# 14_-_ETHERNET_10_100_1000.net
KiCad netlist of a schematic drawn in Altium Designer
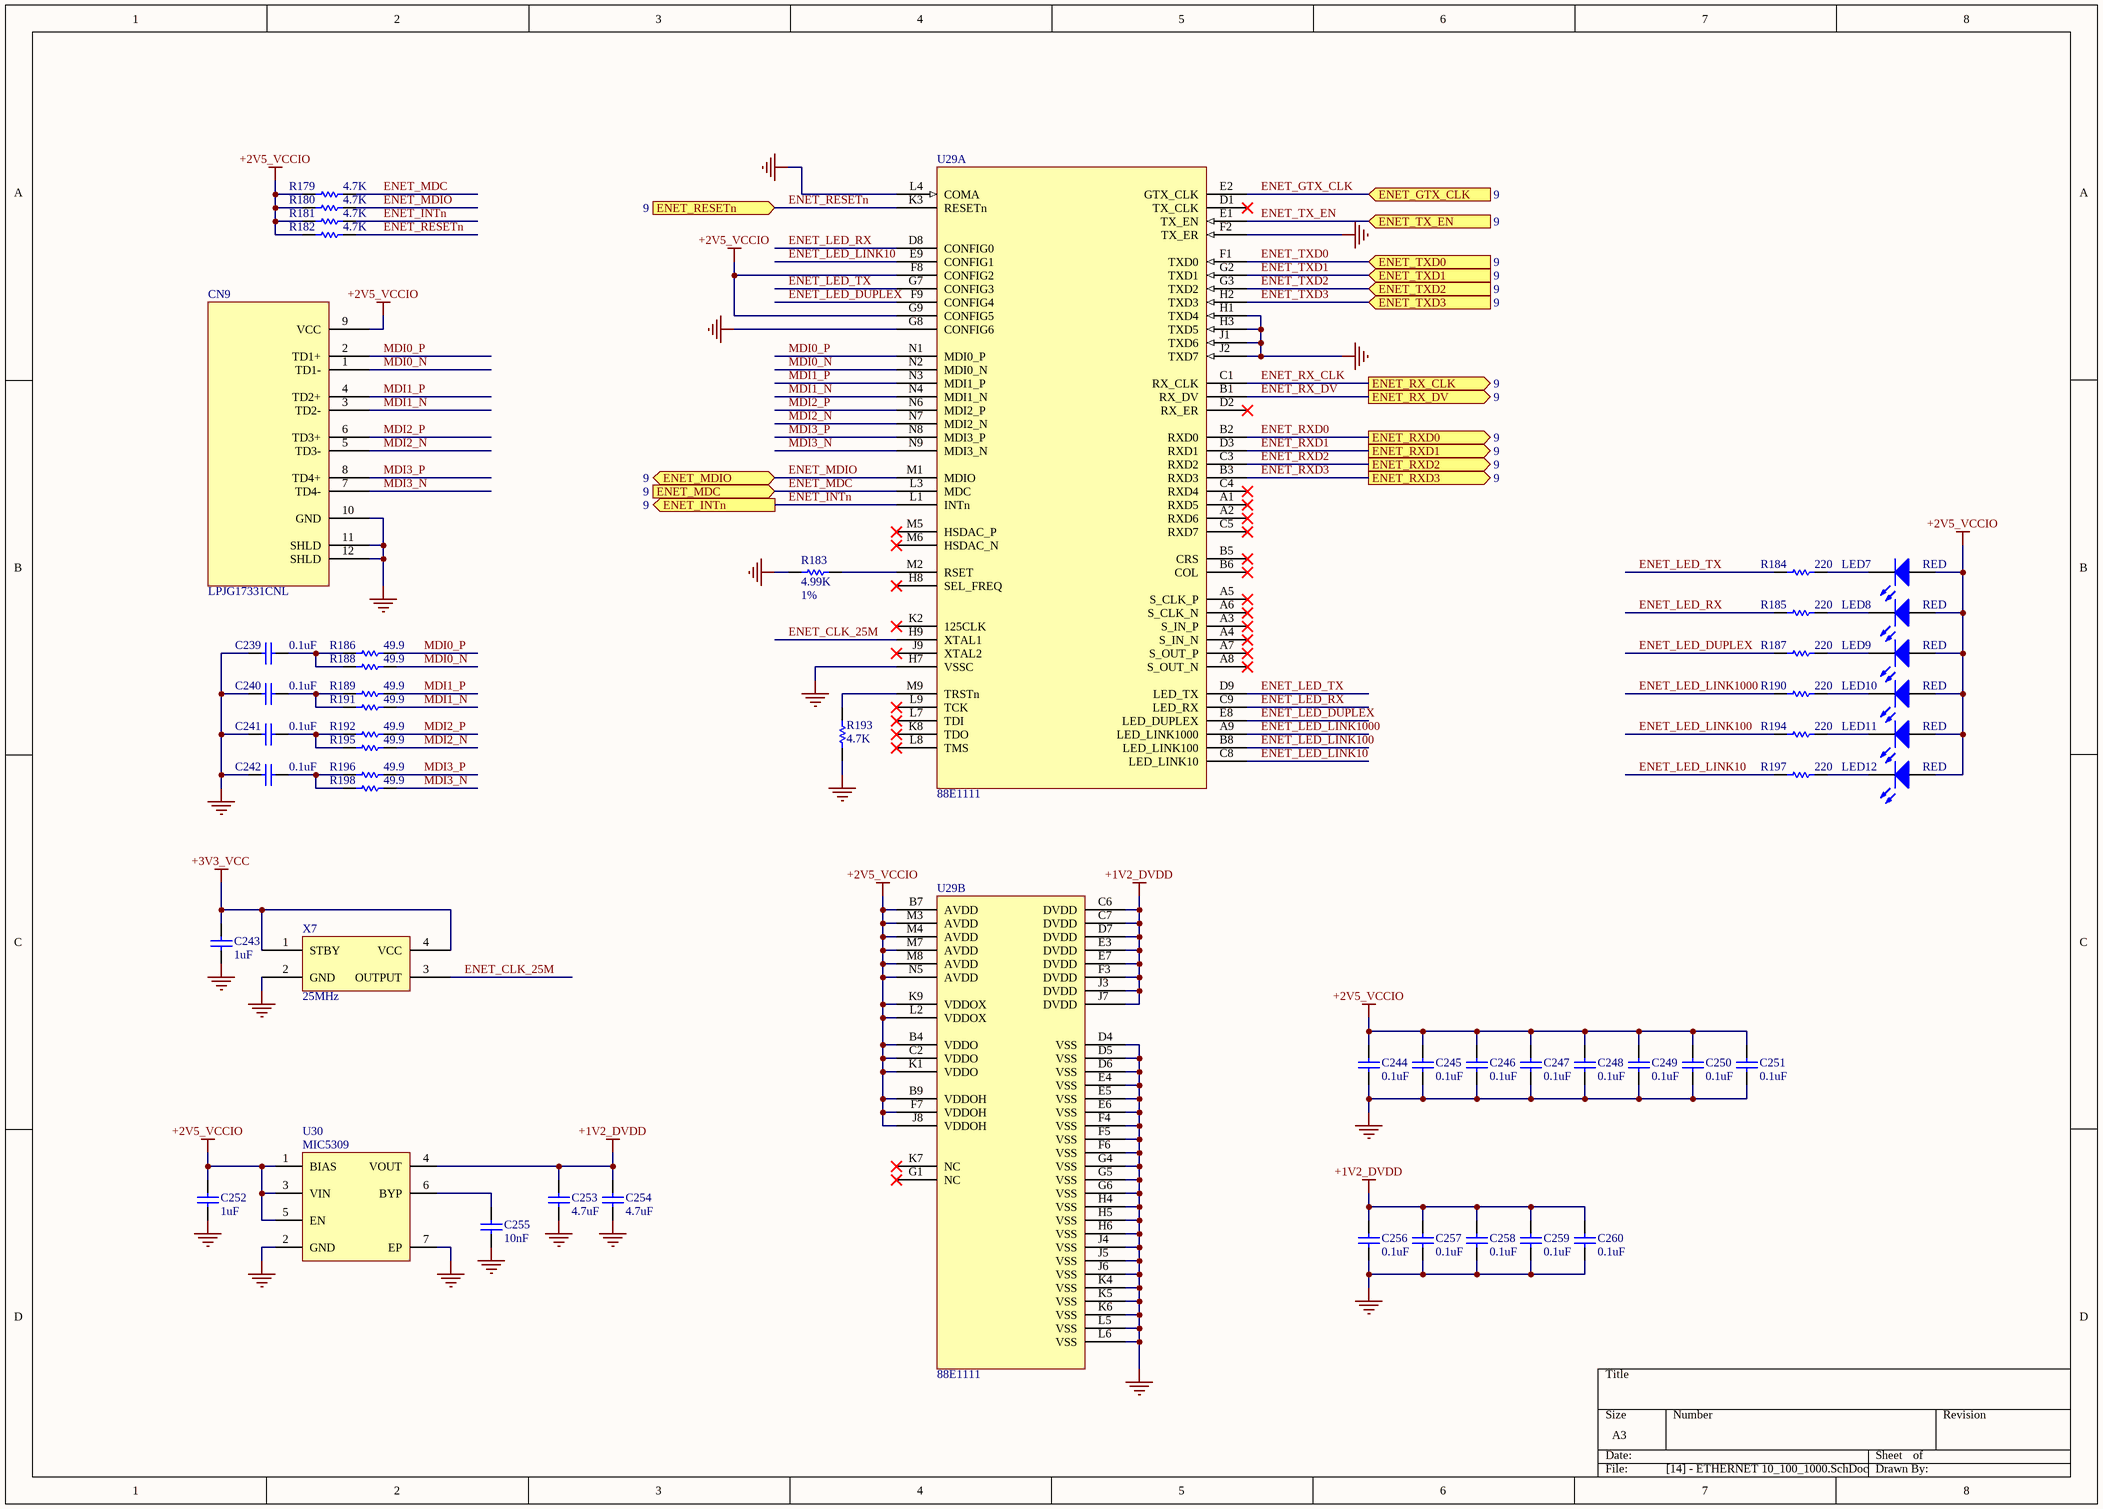
[diagram p0: [14] - ETHERNET 10_100_1000.SchDoc]

(export (version "E")
  (design (tool "Eeschema 10.0.6"))
  (components
    (comp (ref "C239")
      (value "0.1uF")
      (footprint "0402_C")
      (description "Non-Pol SMD Capacitor")
      (libsource (lib "Passive Components") (part "Cap SMD"))
    )
    (comp (ref "C240")
      (value "0.1uF")
      (footprint "0402_C")
      (description "Non-Pol SMD Capacitor")
      (libsource (lib "Passive Components") (part "Cap SMD"))
    )
    (comp (ref "C241")
      (value "0.1uF")
      (footprint "0402_C")
      (description "Non-Pol SMD Capacitor")
      (libsource (lib "Passive Components") (part "Cap SMD"))
    )
    (comp (ref "C242")
      (value "0.1uF")
      (footprint "0402_C")
      (description "Non-Pol SMD Capacitor")
      (libsource (lib "Passive Components") (part "Cap SMD"))
    )
    (comp (ref "C243")
      (value "1uF")
      (footprint "0402_C")
      (description "Non-Pol SMD Capacitor")
      (libsource (lib "Passive Components") (part "Cap SMD"))
    )
    (comp (ref "C244")
      (value "0.1uF")
      (footprint "0402_C")
      (description "Non-Pol SMD Capacitor")
      (libsource (lib "Passive Components") (part "Cap SMD"))
    )
    (comp (ref "C245")
      (value "0.1uF")
      (footprint "0402_C")
      (description "Non-Pol SMD Capacitor")
      (libsource (lib "Passive Components") (part "Cap SMD"))
    )
    (comp (ref "C246")
      (value "0.1uF")
      (footprint "0402_C")
      (description "Non-Pol SMD Capacitor")
      (libsource (lib "Passive Components") (part "Cap SMD"))
    )
    (comp (ref "C247")
      (value "0.1uF")
      (footprint "0402_C")
      (description "Non-Pol SMD Capacitor")
      (libsource (lib "Passive Components") (part "Cap SMD"))
    )
    (comp (ref "C248")
      (value "0.1uF")
      (footprint "0402_C")
      (description "Non-Pol SMD Capacitor")
      (libsource (lib "Passive Components") (part "Cap SMD"))
    )
    (comp (ref "C249")
      (value "0.1uF")
      (footprint "0402_C")
      (description "Non-Pol SMD Capacitor")
      (libsource (lib "Passive Components") (part "Cap SMD"))
    )
    (comp (ref "C250")
      (value "0.1uF")
      (footprint "0402_C")
      (description "Non-Pol SMD Capacitor")
      (libsource (lib "Passive Components") (part "Cap SMD"))
    )
    (comp (ref "C251")
      (value "0.1uF")
      (footprint "0402_C")
      (description "Non-Pol SMD Capacitor")
      (libsource (lib "Passive Components") (part "Cap SMD"))
    )
    (comp (ref "C252")
      (value "1uF")
      (footprint "0805_C")
      (description "Non-Pol SMD Capacitor")
      (libsource (lib "Passive Components") (part "Cap SMD"))
    )
    (comp (ref "C253")
      (value "4.7uF")
      (footprint "0805_C")
      (description "Non-Pol SMD Capacitor")
      (libsource (lib "Passive Components") (part "Cap SMD"))
    )
    (comp (ref "C254")
      (value "4.7uF")
      (footprint "0805_C")
      (description "Non-Pol SMD Capacitor")
      (libsource (lib "Passive Components") (part "Cap SMD"))
    )
    (comp (ref "C255")
      (value "10nF")
      (footprint "0805_C")
      (description "Non-Pol SMD Capacitor")
      (libsource (lib "Passive Components") (part "Cap SMD"))
    )
    (comp (ref "C256")
      (value "0.1uF")
      (footprint "0402_C")
      (description "Non-Pol SMD Capacitor")
      (libsource (lib "Passive Components") (part "Cap SMD"))
    )
    (comp (ref "C257")
      (value "0.1uF")
      (footprint "0402_C")
      (description "Non-Pol SMD Capacitor")
      (libsource (lib "Passive Components") (part "Cap SMD"))
    )
    (comp (ref "C258")
      (value "0.1uF")
      (footprint "0402_C")
      (description "Non-Pol SMD Capacitor")
      (libsource (lib "Passive Components") (part "Cap SMD"))
    )
    (comp (ref "C259")
      (value "0.1uF")
      (footprint "0402_C")
      (description "Non-Pol SMD Capacitor")
      (libsource (lib "Passive Components") (part "Cap SMD"))
    )
    (comp (ref "C260")
      (value "0.1uF")
      (footprint "0402_C")
      (description "Non-Pol SMD Capacitor")
      (libsource (lib "Passive Components") (part "Cap SMD"))
    )
    (comp (ref "CN9")
      (value "LPJG17331CNL")
      (footprint "LPJG17331CNL")
      (description "100/1000 Base-T Modular jack RJ45 With Transformer Tab Up Without Led")
      (libsource (lib "Connectors") (part "LPJG17331CNL"))
    )
    (comp (ref "LED7")
      (value "RED")
      (footprint "LED_0603")
      (description "Typical LED")
      (libsource (lib "Common Components") (part "LED"))
    )
    (comp (ref "LED8")
      (value "RED")
      (footprint "LED_0603")
      (description "Typical LED")
      (libsource (lib "Common Components") (part "LED"))
    )
    (comp (ref "LED9")
      (value "RED")
      (footprint "LED_0603")
      (description "Typical LED")
      (libsource (lib "Common Components") (part "LED"))
    )
    (comp (ref "LED10")
      (value "RED")
      (footprint "LED_0603")
      (description "Typical LED")
      (libsource (lib "Common Components") (part "LED"))
    )
    (comp (ref "LED11")
      (value "RED")
      (footprint "LED_0603")
      (description "Typical LED")
      (libsource (lib "Common Components") (part "LED"))
    )
    (comp (ref "LED12")
      (value "RED")
      (footprint "LED_0603")
      (description "Typical LED")
      (libsource (lib "Common Components") (part "LED"))
    )
    (comp (ref "R179")
      (value "4.7K")
      (footprint "0402_R")
      (description "SMD Resistor")
      (fields (field (name "TOLERANCE") "5%"))
      (libsource (lib "Passive Components") (part "Res SMD"))
    )
    (comp (ref "R180")
      (value "4.7K")
      (footprint "0402_R")
      (description "SMD Resistor")
      (fields (field (name "TOLERANCE") "5%"))
      (libsource (lib "Passive Components") (part "Res SMD"))
    )
    (comp (ref "R181")
      (value "4.7K")
      (footprint "0402_R")
      (description "SMD Resistor")
      (fields (field (name "TOLERANCE") "5%"))
      (libsource (lib "Passive Components") (part "Res SMD"))
    )
    (comp (ref "R182")
      (value "4.7K")
      (footprint "0402_R")
      (description "SMD Resistor")
      (fields (field (name "TOLERANCE") "5%"))
      (libsource (lib "Passive Components") (part "Res SMD"))
    )
    (comp (ref "R183")
      (value "4.99K")
      (footprint "0402_R")
      (description "SMD Resistor")
      (fields (field (name "TOLERANCE") "1%"))
      (libsource (lib "Passive Components") (part "Res SMD"))
    )
    (comp (ref "R184")
      (value "220")
      (footprint "0805_R")
      (description "SMD Resistor")
      (fields (field (name "TOLERANCE") "5%"))
      (libsource (lib "Passive Components") (part "Res SMD"))
    )
    (comp (ref "R185")
      (value "220")
      (footprint "0805_R")
      (description "SMD Resistor")
      (fields (field (name "TOLERANCE") "5%"))
      (libsource (lib "Passive Components") (part "Res SMD"))
    )
    (comp (ref "R186")
      (value "49.9")
      (footprint "0402_R")
      (description "SMD Resistor")
      (fields (field (name "TOLERANCE") "5%"))
      (libsource (lib "Passive Components") (part "Res SMD"))
    )
    (comp (ref "R187")
      (value "220")
      (footprint "0805_R")
      (description "SMD Resistor")
      (fields (field (name "TOLERANCE") "5%"))
      (libsource (lib "Passive Components") (part "Res SMD"))
    )
    (comp (ref "R188")
      (value "49.9")
      (footprint "0402_R")
      (description "SMD Resistor")
      (fields (field (name "TOLERANCE") "5%"))
      (libsource (lib "Passive Components") (part "Res SMD"))
    )
    (comp (ref "R189")
      (value "49.9")
      (footprint "0402_R")
      (description "SMD Resistor")
      (fields (field (name "TOLERANCE") "5%"))
      (libsource (lib "Passive Components") (part "Res SMD"))
    )
    (comp (ref "R190")
      (value "220")
      (footprint "0805_R")
      (description "SMD Resistor")
      (fields (field (name "TOLERANCE") "5%"))
      (libsource (lib "Passive Components") (part "Res SMD"))
    )
    (comp (ref "R191")
      (value "49.9")
      (footprint "0402_R")
      (description "SMD Resistor")
      (fields (field (name "TOLERANCE") "5%"))
      (libsource (lib "Passive Components") (part "Res SMD"))
    )
    (comp (ref "R192")
      (value "49.9")
      (footprint "0402_R")
      (description "SMD Resistor")
      (fields (field (name "TOLERANCE") "5%"))
      (libsource (lib "Passive Components") (part "Res SMD"))
    )
    (comp (ref "R193")
      (value "4.7K")
      (footprint "0402_R")
      (description "SMD Resistor")
      (fields (field (name "TOLERANCE") "5%"))
      (libsource (lib "Passive Components") (part "Res SMD"))
    )
    (comp (ref "R194")
      (value "220")
      (footprint "0805_R")
      (description "SMD Resistor")
      (fields (field (name "TOLERANCE") "5%"))
      (libsource (lib "Passive Components") (part "Res SMD"))
    )
    (comp (ref "R195")
      (value "49.9")
      (footprint "0402_R")
      (description "SMD Resistor")
      (fields (field (name "TOLERANCE") "5%"))
      (libsource (lib "Passive Components") (part "Res SMD"))
    )
    (comp (ref "R196")
      (value "49.9")
      (footprint "0402_R")
      (description "SMD Resistor")
      (fields (field (name "TOLERANCE") "5%"))
      (libsource (lib "Passive Components") (part "Res SMD"))
    )
    (comp (ref "R197")
      (value "220")
      (footprint "0805_R")
      (description "SMD Resistor")
      (fields (field (name "TOLERANCE") "5%"))
      (libsource (lib "Passive Components") (part "Res SMD"))
    )
    (comp (ref "R198")
      (value "49.9")
      (footprint "0402_R")
      (description "SMD Resistor")
      (fields (field (name "TOLERANCE") "5%"))
      (libsource (lib "Passive Components") (part "Res SMD"))
    )
    (comp (ref "U29")
      (value "88E1111")
      (description "Integrated 10/100/1000 Ultra Gigabit Ethernet Transceiver")
      (libsource (lib "Project_schlib") (part "88E1111"))
    )
    (comp (ref "U30")
      (value "MIC5309")
      (footprint "hKeeping:DFN-6")
      (description "Low Vin/Vout 300mA High PSRR ULDO with Ultra-Low IQ")
      (fields (field (name "MANUFACTURER PART NUM") "MIC5309-1.2YMT"))
      (libsource (lib "Project_schlib") (part "MIC5309"))
    )
    (comp (ref "X7")
      (value "25MHz")
      (footprint "OSC_3.2x2.5")
      (description "Crystal Oscillator")
      (libsource (lib "Common Components") (part "XTAL OSC"))
    )
  )
  (nets
    (net (code "1") (name "+1V2_DVDD") (class "Default")
      (node (ref "C253") (pin "2") (pinfunction "2_2") (pintype "passive"))
      (node (ref "C254") (pin "2") (pinfunction "2_2") (pintype "passive"))
      (node (ref "C256") (pin "1") (pinfunction "1_1") (pintype "passive"))
      (node (ref "C257") (pin "1") (pinfunction "1_1") (pintype "passive"))
      (node (ref "C258") (pin "1") (pinfunction "1_1") (pintype "passive"))
      (node (ref "C259") (pin "1") (pinfunction "1_1") (pintype "passive"))
      (node (ref "C260") (pin "1") (pinfunction "1_1") (pintype "passive"))
      (node (ref "U29") (pin "C6") (pinfunction "DVDD_C6") (pintype "power_in"))
      (node (ref "U29") (pin "C7") (pinfunction "DVDD_C7") (pintype "power_in"))
      (node (ref "U29") (pin "D7") (pinfunction "DVDD_D7") (pintype "power_in"))
      (node (ref "U29") (pin "E3") (pinfunction "DVDD_E3") (pintype "power_in"))
      (node (ref "U29") (pin "E7") (pinfunction "DVDD_E7") (pintype "power_in"))
      (node (ref "U29") (pin "F3") (pinfunction "DVDD_F3") (pintype "power_in"))
      (node (ref "U29") (pin "J3") (pinfunction "DVDD_J3") (pintype "power_in"))
      (node (ref "U29") (pin "J7") (pinfunction "DVDD_J7") (pintype "power_in"))
      (node (ref "U30") (pin "4") (pinfunction "VOUT_4") (pintype "power_in"))
    )
    (net (code "2") (name "+2V5_VCCIO") (class "Default")
      (node (ref "C244") (pin "1") (pinfunction "1_1") (pintype "passive"))
      (node (ref "C245") (pin "1") (pinfunction "1_1") (pintype "passive"))
      (node (ref "C246") (pin "1") (pinfunction "1_1") (pintype "passive"))
      (node (ref "C247") (pin "1") (pinfunction "1_1") (pintype "passive"))
      (node (ref "C248") (pin "1") (pinfunction "1_1") (pintype "passive"))
      (node (ref "C249") (pin "1") (pinfunction "1_1") (pintype "passive"))
      (node (ref "C250") (pin "1") (pinfunction "1_1") (pintype "passive"))
      (node (ref "C251") (pin "1") (pinfunction "1_1") (pintype "passive"))
      (node (ref "C252") (pin "2") (pinfunction "2_2") (pintype "passive"))
      (node (ref "CN9") (pin "9") (pinfunction "VCC_9") (pintype "power_in"))
      (node (ref "LED10") (pin "1") (pinfunction "A_1") (pintype "passive"))
      (node (ref "LED11") (pin "1") (pinfunction "A_1") (pintype "passive"))
      (node (ref "LED12") (pin "1") (pinfunction "A_1") (pintype "passive"))
      (node (ref "LED7") (pin "1") (pinfunction "A_1") (pintype "passive"))
      (node (ref "LED8") (pin "1") (pinfunction "A_1") (pintype "passive"))
      (node (ref "LED9") (pin "1") (pinfunction "A_1") (pintype "passive"))
      (node (ref "R179") (pin "2") (pinfunction "2_2") (pintype "passive"))
      (node (ref "R180") (pin "2") (pinfunction "2_2") (pintype "passive"))
      (node (ref "R181") (pin "2") (pinfunction "2_2") (pintype "passive"))
      (node (ref "R182") (pin "2") (pinfunction "2_2") (pintype "passive"))
      (node (ref "U29") (pin "B4") (pinfunction "VDDO_B4") (pintype "power_in"))
      (node (ref "U29") (pin "B7") (pinfunction "AVDD_B7") (pintype "power_in"))
      (node (ref "U29") (pin "B9") (pinfunction "VDDOH_B9") (pintype "power_in"))
      (node (ref "U29") (pin "C2") (pinfunction "VDDO_C2") (pintype "power_in"))
      (node (ref "U29") (pin "F7") (pinfunction "VDDOH_F7") (pintype "power_in"))
      (node (ref "U29") (pin "F8") (pinfunction "CONFIG2_F8") (pintype "passive"))
      (node (ref "U29") (pin "G9") (pinfunction "CONFIG5_G9") (pintype "passive"))
      (node (ref "U29") (pin "J8") (pinfunction "VDDOH_J8") (pintype "power_in"))
      (node (ref "U29") (pin "K1") (pinfunction "VDDO_K1") (pintype "power_in"))
      (node (ref "U29") (pin "K9") (pinfunction "VDDOX_K9") (pintype "power_in"))
      (node (ref "U29") (pin "L2") (pinfunction "VDDOX_L2") (pintype "power_in"))
      (node (ref "U29") (pin "M3") (pinfunction "AVDD_M3") (pintype "power_in"))
      (node (ref "U29") (pin "M4") (pinfunction "AVDD_M4") (pintype "power_in"))
      (node (ref "U29") (pin "M7") (pinfunction "AVDD_M7") (pintype "power_in"))
      (node (ref "U29") (pin "M8") (pinfunction "AVDD_M8") (pintype "power_in"))
      (node (ref "U29") (pin "N5") (pinfunction "AVDD_N5") (pintype "power_in"))
      (node (ref "U30") (pin "1") (pinfunction "BIAS_1") (pintype "power_in"))
      (node (ref "U30") (pin "3") (pinfunction "VIN_3") (pintype "power_in"))
      (node (ref "U30") (pin "5") (pinfunction "EN_5") (pintype "passive"))
    )
    (net (code "3") (name "+3V3_VCC") (class "Default")
      (node (ref "C243") (pin "2") (pinfunction "2_2") (pintype "passive"))
      (node (ref "X7") (pin "1") (pinfunction "STBY_1") (pintype "passive"))
      (node (ref "X7") (pin "4") (pinfunction "VCC_4") (pintype "passive"))
    )
    (net (code "4") (name "/ENET_CLK_25M") (class "Default")
      (node (ref "U29") (pin "H9") (pinfunction "XTAL1_H9") (pintype "passive"))
      (node (ref "X7") (pin "3") (pinfunction "OUTPUT_3") (pintype "passive"))
    )
    (net (code "5") (name "/ENET_GTX_CLK") (class "Default")
      (node (ref "U29") (pin "E2") (pinfunction "GTX_CLK_E2") (pintype "passive"))
    )
    (net (code "6") (name "/ENET_INTn") (class "Default")
      (node (ref "R181") (pin "1") (pinfunction "1_1") (pintype "passive"))
      (node (ref "U29") (pin "L1") (pinfunction "INTn_L1") (pintype "passive"))
    )
    (net (code "7") (name "/ENET_LED_DUPLEX") (class "Default")
      (node (ref "R187") (pin "1") (pinfunction "1_1") (pintype "passive"))
      (node (ref "U29") (pin "E8") (pinfunction "LED_DUPLEX_E8") (pintype "passive"))
      (node (ref "U29") (pin "F9") (pinfunction "CONFIG4_F9") (pintype "passive"))
    )
    (net (code "8") (name "/ENET_LED_LINK10") (class "Default")
      (node (ref "R197") (pin "1") (pinfunction "1_1") (pintype "passive"))
      (node (ref "U29") (pin "C8") (pinfunction "LED_LINK10_C8") (pintype "passive"))
      (node (ref "U29") (pin "E9") (pinfunction "CONFIG1_E9") (pintype "passive"))
    )
    (net (code "9") (name "/ENET_LED_LINK100") (class "Default")
      (node (ref "R194") (pin "1") (pinfunction "1_1") (pintype "passive"))
      (node (ref "U29") (pin "B8") (pinfunction "LED_LINK100_B8") (pintype "passive"))
    )
    (net (code "10") (name "/ENET_LED_LINK1000") (class "Default")
      (node (ref "R190") (pin "1") (pinfunction "1_1") (pintype "passive"))
      (node (ref "U29") (pin "A9") (pinfunction "LED_LINK1000_A9") (pintype "passive"))
    )
    (net (code "11") (name "/ENET_LED_RX") (class "Default")
      (node (ref "R185") (pin "1") (pinfunction "1_1") (pintype "passive"))
      (node (ref "U29") (pin "C9") (pinfunction "LED_RX_C9") (pintype "passive"))
      (node (ref "U29") (pin "D8") (pinfunction "CONFIG0_D8") (pintype "passive"))
    )
    (net (code "12") (name "/ENET_LED_TX") (class "Default")
      (node (ref "R184") (pin "1") (pinfunction "1_1") (pintype "passive"))
      (node (ref "U29") (pin "D9") (pinfunction "LED_TX_D9") (pintype "passive"))
      (node (ref "U29") (pin "G7") (pinfunction "CONFIG3_G7") (pintype "passive"))
    )
    (net (code "13") (name "/ENET_MDC") (class "Default")
      (node (ref "R179") (pin "1") (pinfunction "1_1") (pintype "passive"))
      (node (ref "U29") (pin "L3") (pinfunction "MDC_L3") (pintype "passive"))
    )
    (net (code "14") (name "/ENET_MDIO") (class "Default")
      (node (ref "R180") (pin "1") (pinfunction "1_1") (pintype "passive"))
      (node (ref "U29") (pin "M1") (pinfunction "MDIO_M1") (pintype "passive"))
    )
    (net (code "15") (name "/ENET_RESETn") (class "Default")
      (node (ref "R182") (pin "1") (pinfunction "1_1") (pintype "passive"))
      (node (ref "U29") (pin "K3") (pinfunction "RESETn_K3") (pintype "passive"))
    )
    (net (code "16") (name "/ENET_RXD0") (class "Default")
      (node (ref "U29") (pin "B2") (pinfunction "RXD0_B2") (pintype "passive"))
    )
    (net (code "17") (name "/ENET_RXD1") (class "Default")
      (node (ref "U29") (pin "D3") (pinfunction "RXD1_D3") (pintype "passive"))
    )
    (net (code "18") (name "/ENET_RXD2") (class "Default")
      (node (ref "U29") (pin "C3") (pinfunction "RXD2_C3") (pintype "passive"))
    )
    (net (code "19") (name "/ENET_RXD3") (class "Default")
      (node (ref "U29") (pin "B3") (pinfunction "RXD3_B3") (pintype "passive"))
    )
    (net (code "20") (name "/ENET_RX_CLK") (class "Default")
      (node (ref "U29") (pin "C1") (pinfunction "RX_CLK_C1") (pintype "passive"))
    )
    (net (code "21") (name "/ENET_RX_DV") (class "Default")
      (node (ref "U29") (pin "B1") (pinfunction "RX_DV_B1") (pintype "passive"))
    )
    (net (code "22") (name "/ENET_TXD0") (class "Default")
      (node (ref "U29") (pin "F1") (pinfunction "TXD0_F1") (pintype "input"))
    )
    (net (code "23") (name "/ENET_TXD1") (class "Default")
      (node (ref "U29") (pin "G2") (pinfunction "TXD1_G2") (pintype "input"))
    )
    (net (code "24") (name "/ENET_TXD2") (class "Default")
      (node (ref "U29") (pin "G3") (pinfunction "TXD2_G3") (pintype "input"))
    )
    (net (code "25") (name "/ENET_TXD3") (class "Default")
      (node (ref "U29") (pin "H2") (pinfunction "TXD3_H2") (pintype "input"))
    )
    (net (code "26") (name "/ENET_TX_EN") (class "Default")
      (node (ref "U29") (pin "E1") (pinfunction "TX_EN_E1") (pintype "input"))
    )
    (net (code "27") (name "/MDI0_N") (class "Default")
      (node (ref "CN9") (pin "1") (pinfunction "TD1-_1") (pintype "passive"))
      (node (ref "R188") (pin "1") (pinfunction "1_1") (pintype "passive"))
      (node (ref "U29") (pin "N2") (pinfunction "MDI0_N_N2") (pintype "passive"))
    )
    (net (code "28") (name "/MDI0_P") (class "Default")
      (node (ref "CN9") (pin "2") (pinfunction "TD1+_2") (pintype "passive"))
      (node (ref "R186") (pin "1") (pinfunction "1_1") (pintype "passive"))
      (node (ref "U29") (pin "N1") (pinfunction "MDI0_P_N1") (pintype "passive"))
    )
    (net (code "29") (name "/MDI1_N") (class "Default")
      (node (ref "CN9") (pin "3") (pinfunction "TD2-_3") (pintype "passive"))
      (node (ref "R191") (pin "1") (pinfunction "1_1") (pintype "passive"))
      (node (ref "U29") (pin "N4") (pinfunction "MDI1_N_N4") (pintype "passive"))
    )
    (net (code "30") (name "/MDI1_P") (class "Default")
      (node (ref "CN9") (pin "4") (pinfunction "TD2+_4") (pintype "passive"))
      (node (ref "R189") (pin "1") (pinfunction "1_1") (pintype "passive"))
      (node (ref "U29") (pin "N3") (pinfunction "MDI1_P_N3") (pintype "passive"))
    )
    (net (code "31") (name "/MDI2_N") (class "Default")
      (node (ref "CN9") (pin "5") (pinfunction "TD3-_5") (pintype "passive"))
      (node (ref "R195") (pin "1") (pinfunction "1_1") (pintype "passive"))
      (node (ref "U29") (pin "N7") (pinfunction "MDI2_N_N7") (pintype "passive"))
    )
    (net (code "32") (name "/MDI2_P") (class "Default")
      (node (ref "CN9") (pin "6") (pinfunction "TD3+_6") (pintype "passive"))
      (node (ref "R192") (pin "1") (pinfunction "1_1") (pintype "passive"))
      (node (ref "U29") (pin "N6") (pinfunction "MDI2_P_N6") (pintype "passive"))
    )
    (net (code "33") (name "/MDI3_N") (class "Default")
      (node (ref "CN9") (pin "7") (pinfunction "TD4-_7") (pintype "passive"))
      (node (ref "R198") (pin "1") (pinfunction "1_1") (pintype "passive"))
      (node (ref "U29") (pin "N9") (pinfunction "MDI3_N_N9") (pintype "passive"))
    )
    (net (code "34") (name "/MDI3_P") (class "Default")
      (node (ref "CN9") (pin "8") (pinfunction "TD4+_8") (pintype "passive"))
      (node (ref "R196") (pin "1") (pinfunction "1_1") (pintype "passive"))
      (node (ref "U29") (pin "N8") (pinfunction "MDI3_P_N8") (pintype "passive"))
    )
    (net (code "35") (name "GND") (class "Default")
      (node (ref "C239") (pin "1") (pinfunction "1_1") (pintype "passive"))
      (node (ref "C240") (pin "1") (pinfunction "1_1") (pintype "passive"))
      (node (ref "C241") (pin "1") (pinfunction "1_1") (pintype "passive"))
      (node (ref "C242") (pin "1") (pinfunction "1_1") (pintype "passive"))
      (node (ref "C243") (pin "1") (pinfunction "1_1") (pintype "passive"))
      (node (ref "C244") (pin "2") (pinfunction "2_2") (pintype "passive"))
      (node (ref "C245") (pin "2") (pinfunction "2_2") (pintype "passive"))
      (node (ref "C246") (pin "2") (pinfunction "2_2") (pintype "passive"))
      (node (ref "C247") (pin "2") (pinfunction "2_2") (pintype "passive"))
      (node (ref "C248") (pin "2") (pinfunction "2_2") (pintype "passive"))
      (node (ref "C249") (pin "2") (pinfunction "2_2") (pintype "passive"))
      (node (ref "C250") (pin "2") (pinfunction "2_2") (pintype "passive"))
      (node (ref "C251") (pin "2") (pinfunction "2_2") (pintype "passive"))
      (node (ref "C252") (pin "1") (pinfunction "1_1") (pintype "passive"))
      (node (ref "C253") (pin "1") (pinfunction "1_1") (pintype "passive"))
      (node (ref "C254") (pin "1") (pinfunction "1_1") (pintype "passive"))
      (node (ref "C255") (pin "1") (pinfunction "1_1") (pintype "passive"))
      (node (ref "C256") (pin "2") (pinfunction "2_2") (pintype "passive"))
      (node (ref "C257") (pin "2") (pinfunction "2_2") (pintype "passive"))
      (node (ref "C258") (pin "2") (pinfunction "2_2") (pintype "passive"))
      (node (ref "C259") (pin "2") (pinfunction "2_2") (pintype "passive"))
      (node (ref "C260") (pin "2") (pinfunction "2_2") (pintype "passive"))
      (node (ref "CN9") (pin "10") (pinfunction "GND_10") (pintype "power_in"))
      (node (ref "CN9") (pin "11") (pinfunction "SHLD_11") (pintype "power_in"))
      (node (ref "CN9") (pin "12") (pinfunction "SHLD_12") (pintype "power_in"))
      (node (ref "R183") (pin "2") (pinfunction "2_2") (pintype "passive"))
      (node (ref "R193") (pin "1") (pinfunction "1_1") (pintype "passive"))
      (node (ref "U29") (pin "D4") (pinfunction "VSS_D4") (pintype "power_in"))
      (node (ref "U29") (pin "D5") (pinfunction "VSS_D5") (pintype "power_in"))
      (node (ref "U29") (pin "D6") (pinfunction "VSS_D6") (pintype "power_in"))
      (node (ref "U29") (pin "E4") (pinfunction "VSS_E4") (pintype "power_in"))
      (node (ref "U29") (pin "E5") (pinfunction "VSS_E5") (pintype "power_in"))
      (node (ref "U29") (pin "E6") (pinfunction "VSS_E6") (pintype "power_in"))
      (node (ref "U29") (pin "F2") (pinfunction "TX_ER_F2") (pintype "input"))
      (node (ref "U29") (pin "F4") (pinfunction "VSS_F4") (pintype "power_in"))
      (node (ref "U29") (pin "F5") (pinfunction "VSS_F5") (pintype "power_in"))
      (node (ref "U29") (pin "F6") (pinfunction "VSS_F6") (pintype "power_in"))
      (node (ref "U29") (pin "G4") (pinfunction "VSS_G4") (pintype "power_in"))
      (node (ref "U29") (pin "G5") (pinfunction "VSS_G5") (pintype "power_in"))
      (node (ref "U29") (pin "G6") (pinfunction "VSS_G6") (pintype "power_in"))
      (node (ref "U29") (pin "G8") (pinfunction "CONFIG6_G8") (pintype "passive"))
      (node (ref "U29") (pin "H1") (pinfunction "TXD4_H1") (pintype "input"))
      (node (ref "U29") (pin "H3") (pinfunction "TXD5_H3") (pintype "input"))
      (node (ref "U29") (pin "H4") (pinfunction "VSS_H4") (pintype "power_in"))
      (node (ref "U29") (pin "H5") (pinfunction "VSS_H5") (pintype "power_in"))
      (node (ref "U29") (pin "H6") (pinfunction "VSS_H6") (pintype "power_in"))
      (node (ref "U29") (pin "H7") (pinfunction "VSSC_H7") (pintype "passive"))
      (node (ref "U29") (pin "J1") (pinfunction "TXD6_J1") (pintype "input"))
      (node (ref "U29") (pin "J2") (pinfunction "TXD7_J2") (pintype "input"))
      (node (ref "U29") (pin "J4") (pinfunction "VSS_J4") (pintype "power_in"))
      (node (ref "U29") (pin "J5") (pinfunction "VSS_J5") (pintype "power_in"))
      (node (ref "U29") (pin "J6") (pinfunction "VSS_J6") (pintype "power_in"))
      (node (ref "U29") (pin "K4") (pinfunction "VSS_K4") (pintype "power_in"))
      (node (ref "U29") (pin "K5") (pinfunction "VSS_K5") (pintype "power_in"))
      (node (ref "U29") (pin "K6") (pinfunction "VSS_K6") (pintype "power_in"))
      (node (ref "U29") (pin "L4") (pinfunction "COMA_L4") (pintype "input"))
      (node (ref "U29") (pin "L5") (pinfunction "VSS_L5") (pintype "power_in"))
      (node (ref "U29") (pin "L6") (pinfunction "VSS_L6") (pintype "power_in"))
      (node (ref "U30") (pin "2") (pinfunction "GND_2") (pintype "power_in"))
      (node (ref "U30") (pin "7") (pinfunction "EP_7") (pintype "power_in"))
      (node (ref "X7") (pin "2") (pinfunction "GND_2") (pintype "passive"))
    )
    (net (code "36") (name "Net-(C239-Pad2)") (class "Default")
      (node (ref "C239") (pin "2") (pinfunction "2_2") (pintype "passive"))
      (node (ref "R186") (pin "2") (pinfunction "2_2") (pintype "passive"))
      (node (ref "R188") (pin "2") (pinfunction "2_2") (pintype "passive"))
    )
    (net (code "37") (name "Net-(C240-Pad2)") (class "Default")
      (node (ref "C240") (pin "2") (pinfunction "2_2") (pintype "passive"))
      (node (ref "R189") (pin "2") (pinfunction "2_2") (pintype "passive"))
      (node (ref "R191") (pin "2") (pinfunction "2_2") (pintype "passive"))
    )
    (net (code "38") (name "Net-(C241-Pad2)") (class "Default")
      (node (ref "C241") (pin "2") (pinfunction "2_2") (pintype "passive"))
      (node (ref "R192") (pin "2") (pinfunction "2_2") (pintype "passive"))
      (node (ref "R195") (pin "2") (pinfunction "2_2") (pintype "passive"))
    )
    (net (code "39") (name "Net-(C242-Pad2)") (class "Default")
      (node (ref "C242") (pin "2") (pinfunction "2_2") (pintype "passive"))
      (node (ref "R196") (pin "2") (pinfunction "2_2") (pintype "passive"))
      (node (ref "R198") (pin "2") (pinfunction "2_2") (pintype "passive"))
    )
    (net (code "40") (name "Net-(LED7-K)") (class "Default")
      (node (ref "LED7") (pin "2") (pinfunction "K_2") (pintype "passive"))
      (node (ref "R184") (pin "2") (pinfunction "2_2") (pintype "passive"))
    )
    (net (code "41") (name "Net-(LED8-K)") (class "Default")
      (node (ref "LED8") (pin "2") (pinfunction "K_2") (pintype "passive"))
      (node (ref "R185") (pin "2") (pinfunction "2_2") (pintype "passive"))
    )
    (net (code "42") (name "Net-(LED9-K)") (class "Default")
      (node (ref "LED9") (pin "2") (pinfunction "K_2") (pintype "passive"))
      (node (ref "R187") (pin "2") (pinfunction "2_2") (pintype "passive"))
    )
    (net (code "43") (name "Net-(LED10-K)") (class "Default")
      (node (ref "LED10") (pin "2") (pinfunction "K_2") (pintype "passive"))
      (node (ref "R190") (pin "2") (pinfunction "2_2") (pintype "passive"))
    )
    (net (code "44") (name "Net-(LED11-K)") (class "Default")
      (node (ref "LED11") (pin "2") (pinfunction "K_2") (pintype "passive"))
      (node (ref "R194") (pin "2") (pinfunction "2_2") (pintype "passive"))
    )
    (net (code "45") (name "Net-(LED12-K)") (class "Default")
      (node (ref "LED12") (pin "2") (pinfunction "K_2") (pintype "passive"))
      (node (ref "R197") (pin "2") (pinfunction "2_2") (pintype "passive"))
    )
    (net (code "46") (name "Net-(U29A-RSET)") (class "Default")
      (node (ref "R183") (pin "1") (pinfunction "1_1") (pintype "passive"))
      (node (ref "U29") (pin "M2") (pinfunction "RSET_M2") (pintype "passive"))
    )
    (net (code "47") (name "Net-(U29A-TRSTn)") (class "Default")
      (node (ref "R193") (pin "2") (pinfunction "2_2") (pintype "passive"))
      (node (ref "U29") (pin "M9") (pinfunction "TRSTn_M9") (pintype "passive"))
    )
    (net (code "48") (name "Net-(U30-BYP)") (class "Default")
      (node (ref "C255") (pin "2") (pinfunction "2_2") (pintype "passive"))
      (node (ref "U30") (pin "6") (pinfunction "BYP_6") (pintype "passive"))
    )
    (net (code "49") (name "unconnected-(U29A-125CLK-PadK2)") (class "Default")
      (node (ref "U29") (pin "K2") (pinfunction "125CLK_K2") (pintype "passive+no_connect"))
    )
    (net (code "50") (name "unconnected-(U29A-COL-PadB6)") (class "Default")
      (node (ref "U29") (pin "B6") (pinfunction "COL_B6") (pintype "passive+no_connect"))
    )
    (net (code "51") (name "unconnected-(U29A-CRS-PadB5)") (class "Default")
      (node (ref "U29") (pin "B5") (pinfunction "CRS_B5") (pintype "passive+no_connect"))
    )
    (net (code "52") (name "unconnected-(U29A-HSDAC_N-PadM6)") (class "Default")
      (node (ref "U29") (pin "M6") (pinfunction "HSDAC_N_M6") (pintype "passive+no_connect"))
    )
    (net (code "53") (name "unconnected-(U29A-HSDAC_P-PadM5)") (class "Default")
      (node (ref "U29") (pin "M5") (pinfunction "HSDAC_P_M5") (pintype "passive+no_connect"))
    )
    (net (code "54") (name "unconnected-(U29A-RXD4-PadC4)") (class "Default")
      (node (ref "U29") (pin "C4") (pinfunction "RXD4_C4") (pintype "passive+no_connect"))
    )
    (net (code "55") (name "unconnected-(U29A-RXD5-PadA1)") (class "Default")
      (node (ref "U29") (pin "A1") (pinfunction "RXD5_A1") (pintype "passive+no_connect"))
    )
    (net (code "56") (name "unconnected-(U29A-RXD6-PadA2)") (class "Default")
      (node (ref "U29") (pin "A2") (pinfunction "RXD6_A2") (pintype "passive+no_connect"))
    )
    (net (code "57") (name "unconnected-(U29A-RXD7-PadC5)") (class "Default")
      (node (ref "U29") (pin "C5") (pinfunction "RXD7_C5") (pintype "passive+no_connect"))
    )
    (net (code "58") (name "unconnected-(U29A-RX_ER-PadD2)") (class "Default")
      (node (ref "U29") (pin "D2") (pinfunction "RX_ER_D2") (pintype "passive+no_connect"))
    )
    (net (code "59") (name "unconnected-(U29A-SEL_FREQ-PadH8)") (class "Default")
      (node (ref "U29") (pin "H8") (pinfunction "SEL_FREQ_H8") (pintype "passive+no_connect"))
    )
    (net (code "60") (name "unconnected-(U29A-S_CLK_N-PadA6)") (class "Default")
      (node (ref "U29") (pin "A6") (pinfunction "S_CLK_N_A6") (pintype "passive+no_connect"))
    )
    (net (code "61") (name "unconnected-(U29A-S_CLK_P-PadA5)") (class "Default")
      (node (ref "U29") (pin "A5") (pinfunction "S_CLK_P_A5") (pintype "passive+no_connect"))
    )
    (net (code "62") (name "unconnected-(U29A-S_IN_N-PadA4)") (class "Default")
      (node (ref "U29") (pin "A4") (pinfunction "S_IN_N_A4") (pintype "passive+no_connect"))
    )
    (net (code "63") (name "unconnected-(U29A-S_IN_P-PadA3)") (class "Default")
      (node (ref "U29") (pin "A3") (pinfunction "S_IN_P_A3") (pintype "passive+no_connect"))
    )
    (net (code "64") (name "unconnected-(U29A-S_OUT_N-PadA8)") (class "Default")
      (node (ref "U29") (pin "A8") (pinfunction "S_OUT_N_A8") (pintype "passive+no_connect"))
    )
    (net (code "65") (name "unconnected-(U29A-S_OUT_P-PadA7)") (class "Default")
      (node (ref "U29") (pin "A7") (pinfunction "S_OUT_P_A7") (pintype "passive+no_connect"))
    )
    (net (code "66") (name "unconnected-(U29A-TCK-PadL9)") (class "Default")
      (node (ref "U29") (pin "L9") (pinfunction "TCK_L9") (pintype "passive+no_connect"))
    )
    (net (code "67") (name "unconnected-(U29A-TDI-PadL7)") (class "Default")
      (node (ref "U29") (pin "L7") (pinfunction "TDI_L7") (pintype "passive+no_connect"))
    )
    (net (code "68") (name "unconnected-(U29A-TDO-PadK8)") (class "Default")
      (node (ref "U29") (pin "K8") (pinfunction "TDO_K8") (pintype "passive+no_connect"))
    )
    (net (code "69") (name "unconnected-(U29A-TMS-PadL8)") (class "Default")
      (node (ref "U29") (pin "L8") (pinfunction "TMS_L8") (pintype "passive+no_connect"))
    )
    (net (code "70") (name "unconnected-(U29A-TX_CLK-PadD1)") (class "Default")
      (node (ref "U29") (pin "D1") (pinfunction "TX_CLK_D1") (pintype "passive+no_connect"))
    )
    (net (code "71") (name "unconnected-(U29A-XTAL2-PadJ9)") (class "Default")
      (node (ref "U29") (pin "J9") (pinfunction "XTAL2_J9") (pintype "passive+no_connect"))
    )
    (net (code "72") (name "unconnected-(U29B-NC-PadG1)") (class "Default")
      (node (ref "U29") (pin "G1") (pinfunction "NC_G1") (pintype "power_in+no_connect"))
    )
    (net (code "73") (name "unconnected-(U29B-NC-PadK7)") (class "Default")
      (node (ref "U29") (pin "K7") (pinfunction "NC_K7") (pintype "power_in+no_connect"))
    )
  )
)
